# DAAP.net
KiCad netlist of a schematic drawn in EasyEDA
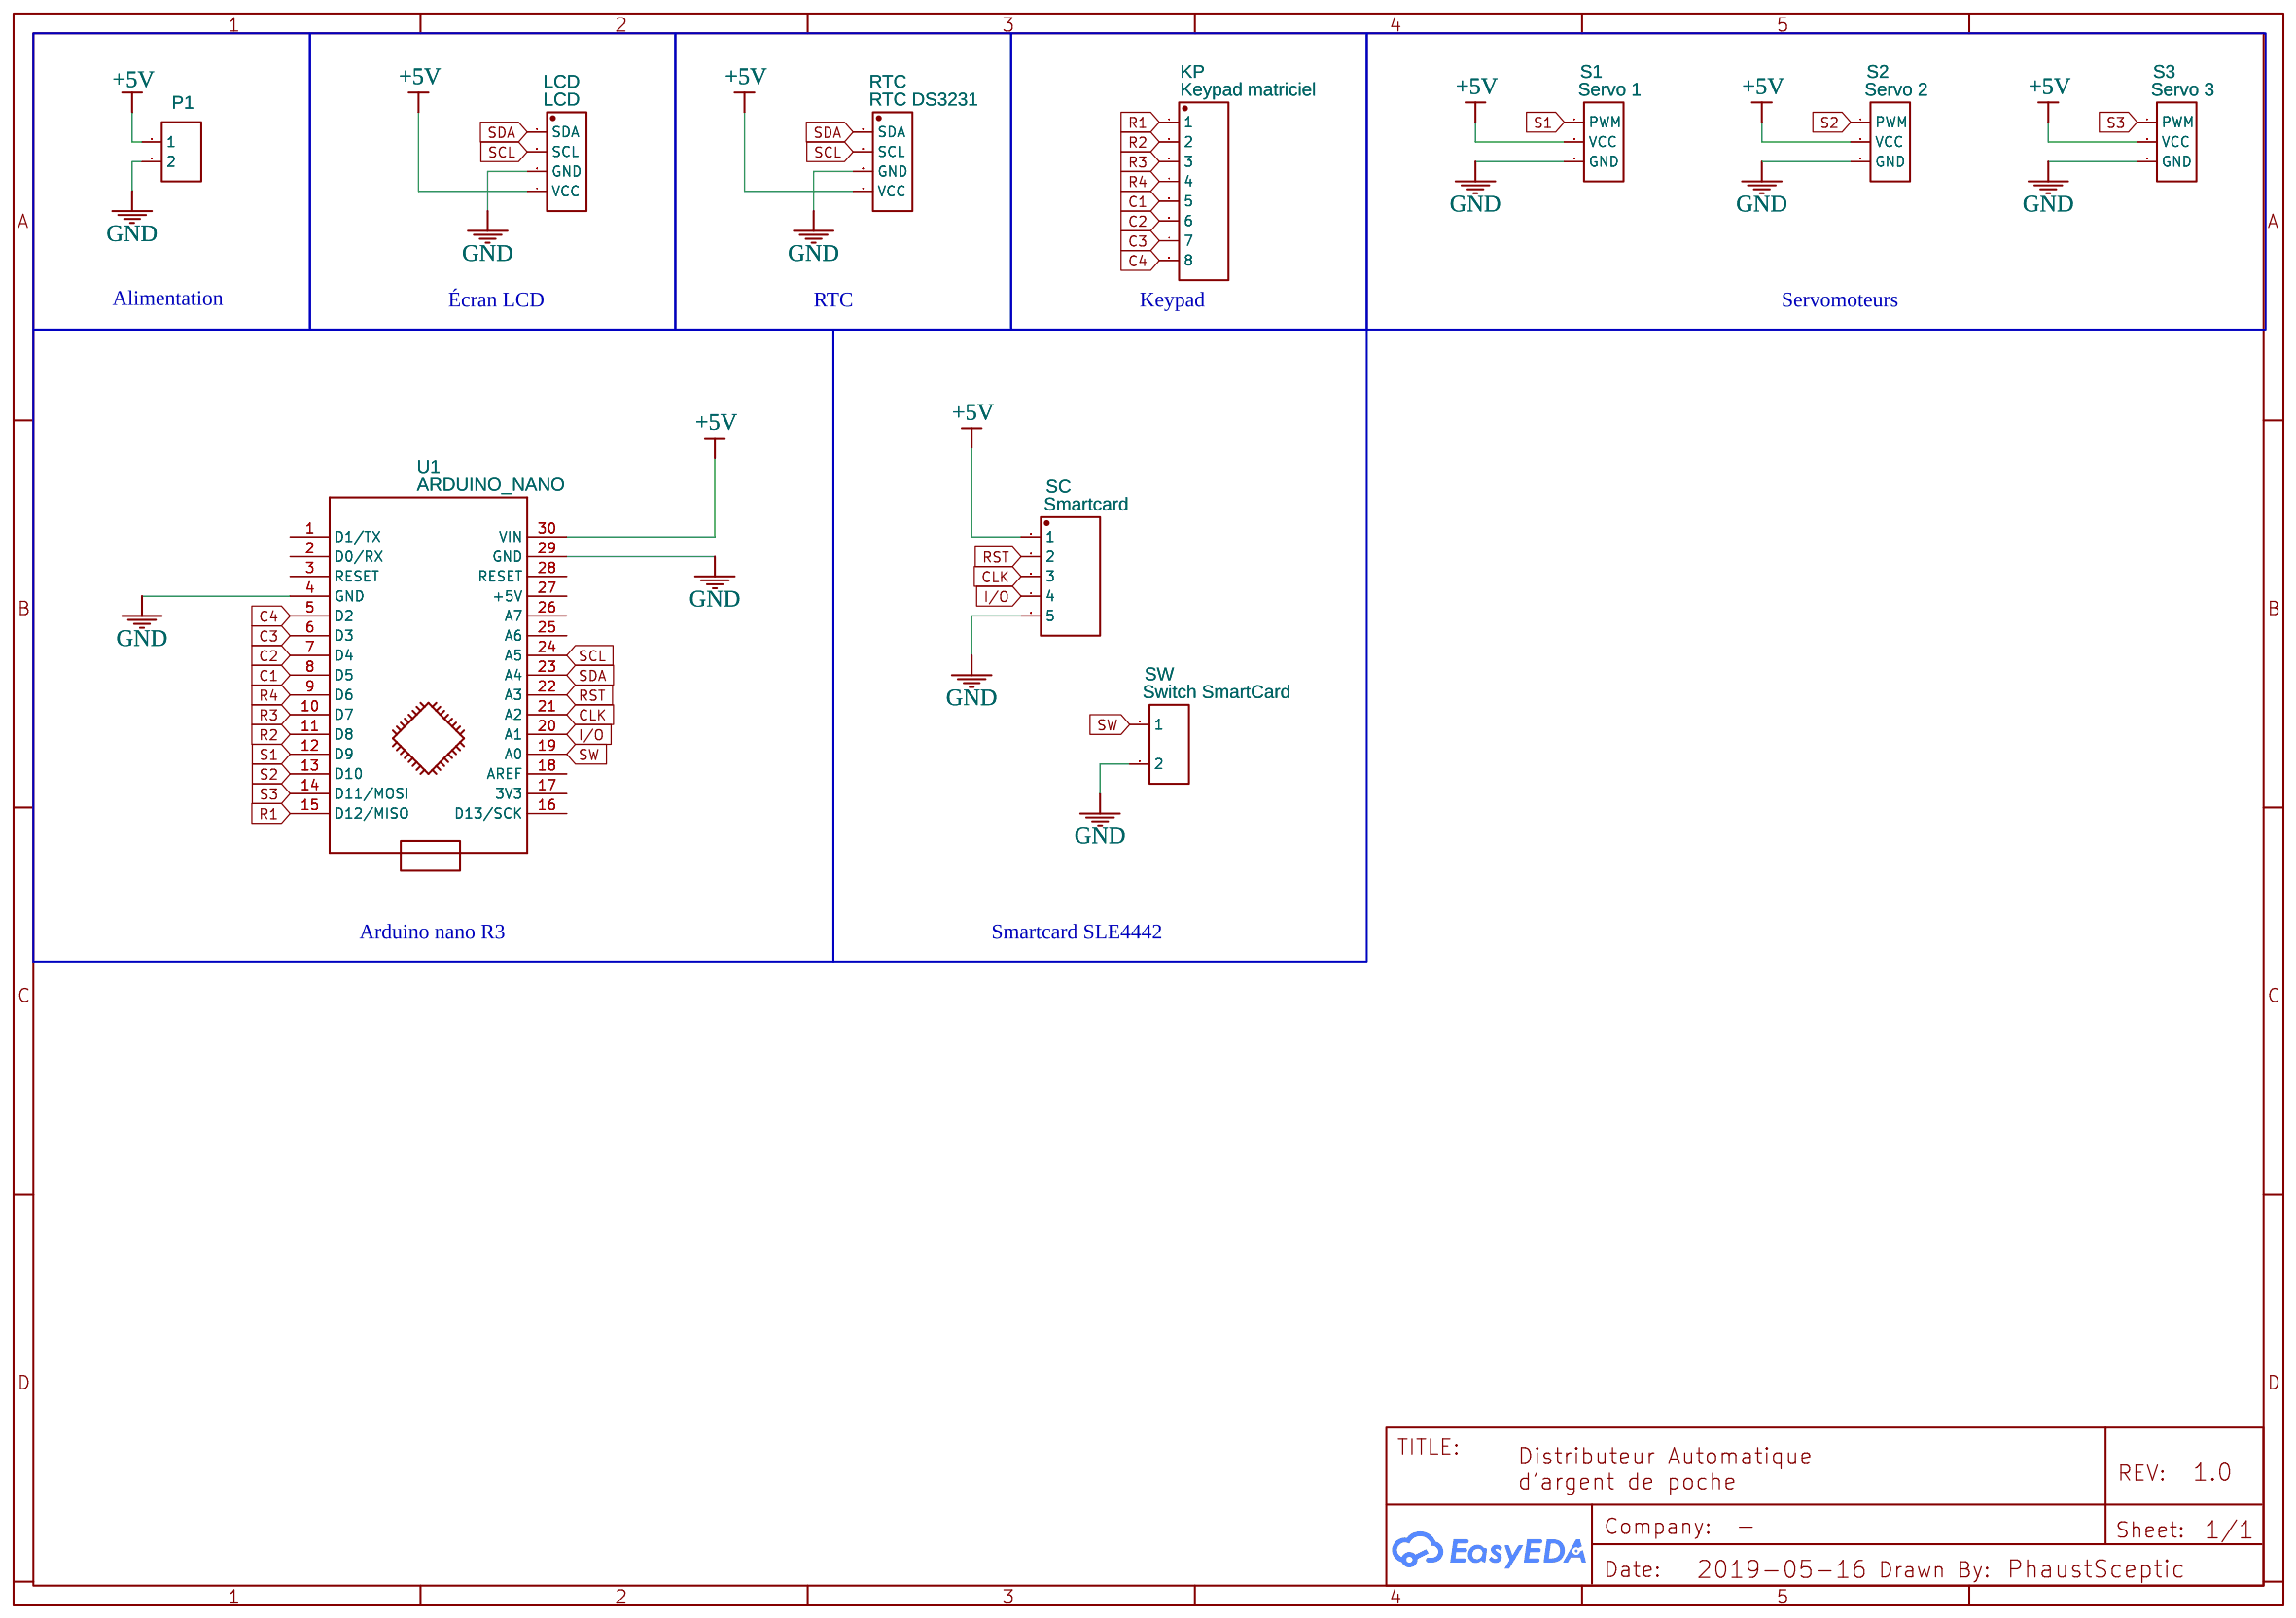
[diagram p0: schematic sheet]

(export (version "E")
  (design (tool "Eeschema 10.0.6"))
  (components
    (comp (ref "KP")
      (value "Keypad matriciel")
      (fields
        (field (name "BOM_Manufacturer Part") "210S-1*8P L=11.6MMGold-plated black")
        (field (name "BOM_Supplier Part") "C124381")
      )
      (libsource (lib "") (part "Unknown_600_90"))
    )
    (comp (ref "LCD")
      (value "LCD")
      (fields
        (field (name "BOM_Manufacturer Part") "210S-1*4P L=11.6MMGold-plated black")
        (field (name "BOM_Supplier Part") "C124378")
      )
      (libsource (lib "") (part "Unknown_275_75"))
    )
    (comp (ref "P1")
      (value "Header-Female-2.54_1x2")
      (fields
        (field (name "BOM_Manufacturer Part") "2.54-1*2PFemale")
        (field (name "BOM_Supplier Part") "C49661")
      )
      (libsource (lib "") (part "Unknown_80_70"))
    )
    (comp (ref "RTC")
      (value "RTC DS3231")
      (fields
        (field (name "BOM_Manufacturer Part") "210S-1*4P L=11.6MMGold-plated black")
        (field (name "BOM_Supplier Part") "C124378")
      )
      (libsource (lib "") (part "Unknown_440_75"))
    )
    (comp (ref "S1")
      (value "Servo 1")
      (fields
        (field (name "BOM_Manufacturer Part") "Header2.54mm 1*3P")
        (field (name "BOM_Supplier Part") "C49257")
      )
      (libsource (lib "") (part "Unknown_800_65"))
    )
    (comp (ref "S2")
      (value "Servo 2")
      (fields
        (field (name "BOM_Manufacturer Part") "Header2.54mm 1*3P")
        (field (name "BOM_Supplier Part") "C49257")
      )
      (libsource (lib "") (part "Unknown_945_65"))
    )
    (comp (ref "S3")
      (value "Servo 3")
      (fields
        (field (name "BOM_Manufacturer Part") "Header2.54mm 1*3P")
        (field (name "BOM_Supplier Part") "C49257")
      )
      (libsource (lib "") (part "Unknown_1090_65"))
    )
    (comp (ref "SC")
      (value "Smartcard")
      (fields
        (field (name "BOM_Manufacturer Part") "210S-1*5P L=11.6MMGold-plated black")
        (field (name "BOM_Supplier Part") "C124379")
      )
      (libsource (lib "") (part "Unknown_530_285"))
    )
    (comp (ref "SW")
      (value "Switch SmartCard")
      (fields (field (name "BOM_Manufacturer Part") "826629-2") (field (name "BOM_Supplier Part") "C86471"))
      (libsource (lib "") (part "Unknown_580_370"))
    )
    (comp (ref "U1")
      (value "ARDUINO_NANO")
      (fields (field (name "BOM_Manufacturer Part") "?"))
      (libsource (lib "") (part "Unknown_210_340"))
    )
  )
  (nets
    (net (code "1") (name "+5V") (class "Default")
      (node (ref "LCD") (pin "4") (pinfunction "VCC_4") (pintype "unspecified"))
      (node (ref "P1") (pin "1") (pinfunction "1_1") (pintype "input"))
      (node (ref "RTC") (pin "4") (pinfunction "VCC_4") (pintype "unspecified"))
      (node (ref "S1") (pin "2") (pinfunction "VCC_2") (pintype "input"))
      (node (ref "S2") (pin "2") (pinfunction "VCC_2") (pintype "input"))
      (node (ref "S3") (pin "2") (pinfunction "VCC_2") (pintype "input"))
      (node (ref "SC") (pin "1") (pinfunction "1_1") (pintype "unspecified"))
      (node (ref "U1") (pin "30") (pinfunction "VIN_30") (pintype "unspecified"))
    )
    (net (code "2") (name "C1") (class "Default")
      (node (ref "KP") (pin "5") (pinfunction "5_5") (pintype "unspecified"))
      (node (ref "U1") (pin "8") (pinfunction "D5_8") (pintype "unspecified"))
    )
    (net (code "3") (name "C2") (class "Default")
      (node (ref "KP") (pin "6") (pinfunction "6_6") (pintype "unspecified"))
      (node (ref "U1") (pin "7") (pinfunction "D4_7") (pintype "unspecified"))
    )
    (net (code "4") (name "C3") (class "Default")
      (node (ref "KP") (pin "7") (pinfunction "7_7") (pintype "unspecified"))
      (node (ref "U1") (pin "6") (pinfunction "D3_6") (pintype "unspecified"))
    )
    (net (code "5") (name "C4") (class "Default")
      (node (ref "KP") (pin "8") (pinfunction "8_8") (pintype "unspecified"))
      (node (ref "U1") (pin "5") (pinfunction "D2_5") (pintype "unspecified"))
    )
    (net (code "6") (name "CLK") (class "Default")
      (node (ref "SC") (pin "3") (pinfunction "3_3") (pintype "unspecified"))
      (node (ref "U1") (pin "21") (pinfunction "A2_21") (pintype "unspecified"))
    )
    (net (code "7") (name "GND") (class "Default")
      (node (ref "LCD") (pin "3") (pinfunction "GND_3") (pintype "unspecified"))
      (node (ref "P1") (pin "2") (pinfunction "2_2") (pintype "input"))
      (node (ref "RTC") (pin "3") (pinfunction "GND_3") (pintype "unspecified"))
      (node (ref "S1") (pin "3") (pinfunction "GND_3") (pintype "input"))
      (node (ref "S2") (pin "3") (pinfunction "GND_3") (pintype "input"))
      (node (ref "S3") (pin "3") (pinfunction "GND_3") (pintype "input"))
      (node (ref "SC") (pin "5") (pinfunction "5_5") (pintype "unspecified"))
      (node (ref "SW") (pin "2") (pinfunction "2_2") (pintype "unspecified"))
      (node (ref "U1") (pin "29") (pinfunction "GND_29") (pintype "unspecified"))
      (node (ref "U1") (pin "4") (pinfunction "GND_4") (pintype "unspecified"))
    )
    (net (code "8") (name "I{slash}O") (class "Default")
      (node (ref "SC") (pin "4") (pinfunction "4_4") (pintype "unspecified"))
      (node (ref "U1") (pin "20") (pinfunction "A1_20") (pintype "unspecified"))
    )
    (net (code "9") (name "R1") (class "Default")
      (node (ref "KP") (pin "1") (pinfunction "1_1") (pintype "unspecified"))
      (node (ref "U1") (pin "15") (pinfunction "D12/MISO_15") (pintype "unspecified"))
    )
    (net (code "10") (name "R2") (class "Default")
      (node (ref "KP") (pin "2") (pinfunction "2_2") (pintype "unspecified"))
      (node (ref "U1") (pin "11") (pinfunction "D8_11") (pintype "unspecified"))
    )
    (net (code "11") (name "R3") (class "Default")
      (node (ref "KP") (pin "3") (pinfunction "3_3") (pintype "unspecified"))
      (node (ref "U1") (pin "10") (pinfunction "D7_10") (pintype "unspecified"))
    )
    (net (code "12") (name "R4") (class "Default")
      (node (ref "KP") (pin "4") (pinfunction "4_4") (pintype "unspecified"))
      (node (ref "U1") (pin "9") (pinfunction "D6_9") (pintype "unspecified"))
    )
    (net (code "13") (name "RST") (class "Default")
      (node (ref "SC") (pin "2") (pinfunction "2_2") (pintype "unspecified"))
      (node (ref "U1") (pin "22") (pinfunction "A3_22") (pintype "unspecified"))
    )
    (net (code "14") (name "S1") (class "Default")
      (node (ref "S1") (pin "1") (pinfunction "PWM_1") (pintype "input"))
      (node (ref "U1") (pin "12") (pinfunction "D9_12") (pintype "unspecified"))
    )
    (net (code "15") (name "S2") (class "Default")
      (node (ref "S2") (pin "1") (pinfunction "PWM_1") (pintype "input"))
      (node (ref "U1") (pin "13") (pinfunction "D10_13") (pintype "unspecified"))
    )
    (net (code "16") (name "S3") (class "Default")
      (node (ref "S3") (pin "1") (pinfunction "PWM_1") (pintype "input"))
      (node (ref "U1") (pin "14") (pinfunction "D11/MOSI_14") (pintype "unspecified"))
    )
    (net (code "17") (name "SCL") (class "Default")
      (node (ref "LCD") (pin "2") (pinfunction "SCL_2") (pintype "unspecified"))
      (node (ref "RTC") (pin "2") (pinfunction "SCL_2") (pintype "unspecified"))
      (node (ref "U1") (pin "24") (pinfunction "A5_24") (pintype "unspecified"))
    )
    (net (code "18") (name "SDA") (class "Default")
      (node (ref "LCD") (pin "1") (pinfunction "SDA_1") (pintype "unspecified"))
      (node (ref "RTC") (pin "1") (pinfunction "SDA_1") (pintype "unspecified"))
      (node (ref "U1") (pin "23") (pinfunction "A4_23") (pintype "unspecified"))
    )
    (net (code "19") (name "SW") (class "Default")
      (node (ref "SW") (pin "1") (pinfunction "1_1") (pintype "unspecified"))
      (node (ref "U1") (pin "19") (pinfunction "A0_19") (pintype "unspecified"))
    )
    (net (code "20") (name "unconnected-(U1-+5V-Pad27)") (class "Default")
      (node (ref "U1") (pin "27") (pinfunction "+5V_27") (pintype "unspecified"))
    )
    (net (code "21") (name "unconnected-(U1-3V3-Pad17)") (class "Default")
      (node (ref "U1") (pin "17") (pinfunction "3V3_17") (pintype "unspecified"))
    )
    (net (code "22") (name "unconnected-(U1-A6-Pad25)") (class "Default")
      (node (ref "U1") (pin "25") (pinfunction "A6_25") (pintype "unspecified"))
    )
    (net (code "23") (name "unconnected-(U1-A7-Pad26)") (class "Default")
      (node (ref "U1") (pin "26") (pinfunction "A7_26") (pintype "unspecified"))
    )
    (net (code "24") (name "unconnected-(U1-AREF-Pad18)") (class "Default")
      (node (ref "U1") (pin "18") (pinfunction "AREF_18") (pintype "unspecified"))
    )
    (net (code "25") (name "unconnected-(U1-D0{slash}RX-Pad2)") (class "Default")
      (node (ref "U1") (pin "2") (pinfunction "D0/RX_2") (pintype "unspecified"))
    )
    (net (code "26") (name "unconnected-(U1-D1{slash}TX-Pad1)") (class "Default")
      (node (ref "U1") (pin "1") (pinfunction "D1/TX_1") (pintype "unspecified"))
    )
    (net (code "27") (name "unconnected-(U1-D13{slash}SCK-Pad16)") (class "Default")
      (node (ref "U1") (pin "16") (pinfunction "D13/SCK_16") (pintype "unspecified"))
    )
    (net (code "28") (name "unconnected-(U1-RESET-Pad3)") (class "Default")
      (node (ref "U1") (pin "3") (pinfunction "RESET_3") (pintype "unspecified"))
    )
    (net (code "29") (name "unconnected-(U1-RESET-Pad28)") (class "Default")
      (node (ref "U1") (pin "28") (pinfunction "RESET_28") (pintype "unspecified"))
    )
  )
)
